# LCD_RGB.net
KiCad netlist of a schematic drawn in Altium Designer
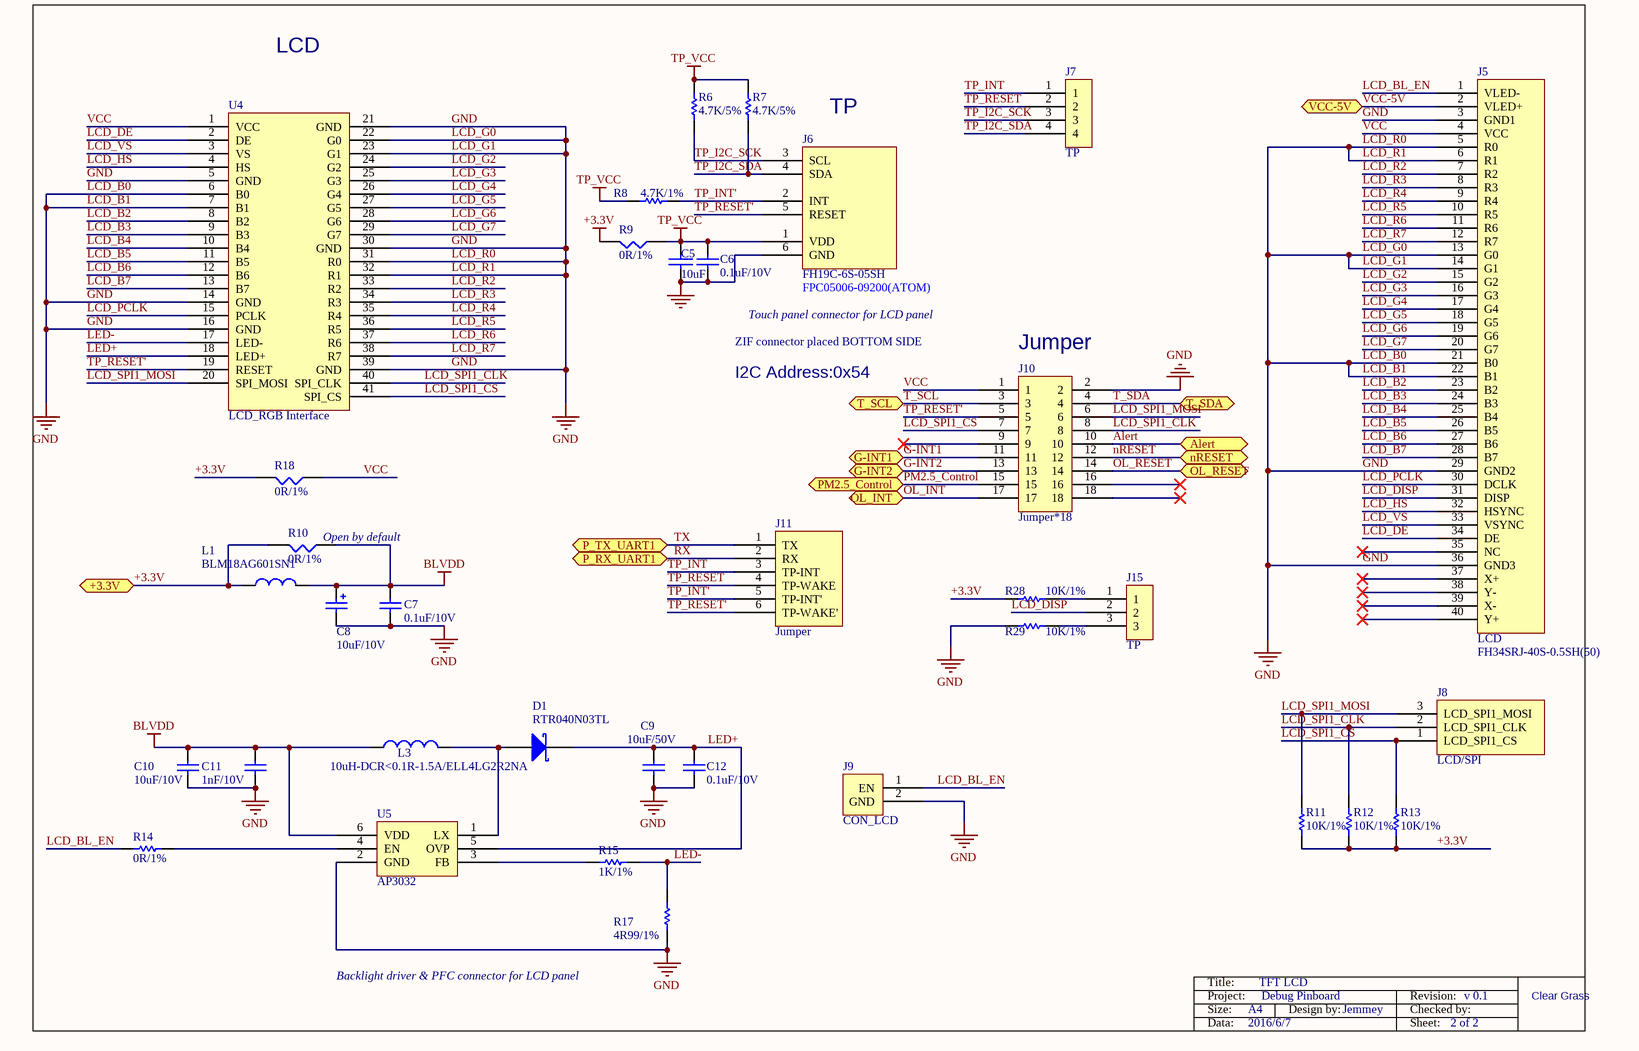
[diagram p0: LCD_RGB.SchDoc]

(export (version "E")
  (design (tool "Eeschema 10.0.6"))
  (components
    (comp (ref "C5")
      (value "10uF")
      (footprint "0603C")
      (description "厂家：Murata，型号：GRM1555C1H120JA01D")
      (libsource (lib "Amber") (part "CAP"))
    )
    (comp (ref "C6")
      (value "0.1uF/10V")
      (footprint "0402C")
      (description "Capacitor")
      (fields (field (name "PUBLISHER") "Altium Limited"))
      (libsource (lib "Miscellaneous Devices") (part "CAP"))
    )
    (comp (ref "C7")
      (value "0.1uF/10V")
      (footprint "0402C")
      (description "Capacitor")
      (fields (field (name "PUBLISHER") "Altium Limited"))
      (libsource (lib "Miscellaneous Devices") (part "Cap"))
    )
    (comp (ref "C8")
      (value "10uF/10V")
      (footprint "0603C")
      (description "Polarized Capacitor (Radial)")
      (fields (field (name "PUBLISHER") "Altium Limited"))
      (libsource (lib "Miscellaneous Devices") (part "Cap Pol1"))
    )
    (comp (ref "C9")
      (value "10uF/50V")
      (footprint "0603C")
      (description "厂家：Murata，型号：")
      (fields (field (name "PUBLISHER") "Altium Limited"))
      (libsource (lib "Miscellaneous Devices") (part "CAP"))
    )
    (comp (ref "C10")
      (value "10uF/10V")
      (footprint "0603C")
      (description "Capacitor")
      (fields (field (name "PUBLISHER") "Altium Limited"))
      (libsource (lib "Miscellaneous Devices") (part "CAP"))
    )
    (comp (ref "C11")
      (value "1nF/10V")
      (footprint "0402C")
      (description "Capacitor")
      (fields (field (name "PUBLISHER") "Altium Limited"))
      (libsource (lib "Miscellaneous Devices") (part "CAP"))
    )
    (comp (ref "C12")
      (value "0.1uF/10V")
      (footprint "0402C")
      (description "厂家：Murata，型号：")
      (fields (field (name "PUBLISHER") "Altium Limited"))
      (libsource (lib "*") (part "CAP"))
    )
    (comp (ref "D1")
      (value "RTR040N03TL")
      (footprint "TUMD2M")
      (description "Schottky Diode")
      (fields (field (name "PUBLISHER") "Altium Limited"))
      (libsource (lib "Miscellaneous Devices") (part "D Schottky"))
    )
    (comp (ref "J5")
      (value "LCD")
      (footprint "FPC_CON40-BACK-IRS")
      (libsource (lib "Debug Pinborad_1") (part "FPC60_1"))
    )
    (comp (ref "J6")
      (value "FH19C-6S-05SH")
      (footprint "FPC_CON6-BACK-MOLEX")
      (description "ZIF connector placed bottom side")
      (libsource (lib "MB1166") (part "FH19C-6S-05SH"))
    )
    (comp (ref "J7")
      (value "TP")
      (footprint "FPC_CON4-1MM-MOLEX")
      (description "Jumper")
      (libsource (lib "Bran PinBoard") (part "Jumper_uart"))
    )
    (comp (ref "J8")
      (value "LCD/SPI")
      (footprint "2.54*3")
      (description "Jumper")
      (libsource (lib "Debug Pinborad") (part "Jumper"))
    )
    (comp (ref "J9")
      (value "CON_LCD")
      (footprint "2.54*2")
      (libsource (lib "Debug Pinborad") (part "CON_LCD"))
    )
    (comp (ref "J10")
      (value "Jumper*18")
      (footprint "2.54*18")
      (libsource (lib "Bran PinBoard") (part "Jumper*18"))
    )
    (comp (ref "J11")
      (value "Jumper")
      (footprint "2.54*2 *3")
      (libsource (lib "Bran PinBoard_1") (part "Jumper_uart"))
    )
    (comp (ref "J15")
      (value "TP")
      (footprint "2.54*3")
      (description "Jumper")
      (libsource (lib "") (part "Jumper_uart_1"))
    )
    (comp (ref "L1")
      (value "BLM18AG601SN1")
      (footprint "0603R")
      (description "厂家：MURATA，型号：BLM18AG601SN1")
      (libsource (lib "Amber") (part "CHOKE"))
    )
    (comp (ref "L3")
      (value "10uH-DCR<0.1R-1.5A/ELL4LG2R2NA")
      (footprint "INDM4040X18N")
      (description "Inductor")
      (fields (field (name "PUBLISHER") "Altium Limited"))
      (libsource (lib "Miscellaneous Devices") (part "Inductor"))
    )
    (comp (ref "R6")
      (value "4.7K/5%")
      (footprint "0402R")
      (description "厂家：Yageo，型号：")
      (fields (field (name "PUBLISHER") "Altium Limited"))
      (libsource (lib "*") (part "Res1"))
    )
    (comp (ref "R7")
      (value "4.7K/5%")
      (footprint "0402R")
      (description "厂家：Yageo，型号：")
      (fields (field (name "PUBLISHER") "Altium Limited"))
      (libsource (lib "*") (part "Res1"))
    )
    (comp (ref "R8")
      (value "4.7K/1%")
      (footprint "0402R")
      (description "厂家：Yageo，型号：")
      (fields (field (name "PUBLISHER") "Altium Limited"))
      (libsource (lib "*") (part "Res1"))
    )
    (comp (ref "R9")
      (value "0R/1%")
      (footprint "0603R")
      (description "厂家：Yageo，型号：RC0402FR-070RL")
      (libsource (lib "*") (part "RES1"))
    )
    (comp (ref "R10")
      (value "0R/1%")
      (footprint "0603R")
      (description "厂家：Yageo，型号：RC0402FR-070RL")
      (libsource (lib "*") (part "RES1"))
    )
    (comp (ref "R11")
      (value "10K/1%")
      (footprint "0402R")
      (description "厂家：Yageo，型号：")
      (fields (field (name "PUBLISHER") "Altium Limited"))
      (libsource (lib "*") (part "Res1"))
    )
    (comp (ref "R12")
      (value "10K/1%")
      (footprint "0402R")
      (description "厂家：Yageo，型号：")
      (fields (field (name "PUBLISHER") "Altium Limited"))
      (libsource (lib "*") (part "Res1"))
    )
    (comp (ref "R13")
      (value "10K/1%")
      (footprint "0402R")
      (description "厂家：Yageo，型号：")
      (fields (field (name "PUBLISHER") "Altium Limited"))
      (libsource (lib "*") (part "Res1"))
    )
    (comp (ref "R14")
      (value "0R/1%")
      (footprint "0402R")
      (description "Resistor")
      (fields (field (name "PUBLISHER") "Altium Limited"))
      (libsource (lib "Miscellaneous Devices") (part "Res1"))
    )
    (comp (ref "R15")
      (value "1K/1%")
      (footprint "0402R")
      (description "Resistor")
      (fields (field (name "PUBLISHER") "Altium Limited"))
      (libsource (lib "Miscellaneous Devices") (part "Res1"))
    )
    (comp (ref "R17")
      (value "4R99/1%")
      (footprint "0402R")
      (description "Resistor")
      (fields (field (name "PUBLISHER") "Altium Limited"))
      (libsource (lib "Miscellaneous Devices") (part "Res1"))
    )
    (comp (ref "R18")
      (value "0R/1%")
      (footprint "0603R")
      (description "厂家：Yageo，型号：RC0402FR-070RL")
      (libsource (lib "*") (part "RES1"))
    )
    (comp (ref "R28")
      (value "10K/1%")
      (footprint "0402R")
      (description "厂家：Yageo，型号：")
      (fields (field (name "PUBLISHER") "Altium Limited"))
      (libsource (lib "*") (part "Res1"))
    )
    (comp (ref "R29")
      (value "10K/1%")
      (footprint "0402R")
      (description "厂家：Yageo，型号：")
      (fields (field (name "PUBLISHER") "Altium Limited"))
      (libsource (lib "*") (part "Res1"))
    )
    (comp (ref "U4")
      (value "LCD_RGB Interface")
      (footprint "FPC_CON41-0.3MM-HRS")
      (libsource (lib "Debug Pinborad_1") (part "LCD_RGB Interface"))
    )
    (comp (ref "U5")
      (value "AP3032")
      (footprint "SOT23-6-L")
      (libsource (lib "Debug Pinborad") (part "AP3032"))
    )
  )
  (nets
    (net (code "1") (name "+3.3V") (class "Default")
      (node (ref "L1") (pin "1") (pinfunction "1_1") (pintype "passive"))
      (node (ref "R10") (pin "2") (pinfunction "2_2") (pintype "passive"))
      (node (ref "R11") (pin "1") (pinfunction "1_1") (pintype "passive"))
      (node (ref "R12") (pin "1") (pinfunction "1_1") (pintype "passive"))
      (node (ref "R13") (pin "1") (pinfunction "1_1") (pintype "passive"))
      (node (ref "R18") (pin "2") (pinfunction "2_2") (pintype "passive"))
      (node (ref "R28") (pin "2") (pinfunction "2_2") (pintype "passive"))
      (node (ref "R9") (pin "2") (pinfunction "2_2") (pintype "passive"))
    )
    (net (code "2") (name "/Alert") (class "Default")
      (node (ref "J10") (pin "10") (pinfunction "10_10") (pintype "passive"))
    )
    (net (code "3") (name "/G-INT1") (class "Default")
      (node (ref "J10") (pin "11") (pinfunction "11_11") (pintype "passive"))
    )
    (net (code "4") (name "/G-INT2") (class "Default")
      (node (ref "J10") (pin "13") (pinfunction "13_13") (pintype "passive"))
    )
    (net (code "5") (name "/LCD_B2") (class "Default")
      (node (ref "J5") (pin "23") (pinfunction "B2_23") (pintype "passive"))
      (node (ref "U4") (pin "8") (pinfunction "B2_8") (pintype "passive"))
    )
    (net (code "6") (name "/LCD_B3") (class "Default")
      (node (ref "J5") (pin "24") (pinfunction "B3_24") (pintype "passive"))
      (node (ref "U4") (pin "9") (pinfunction "B3_9") (pintype "passive"))
    )
    (net (code "7") (name "/LCD_B4") (class "Default")
      (node (ref "J5") (pin "25") (pinfunction "B4_25") (pintype "passive"))
      (node (ref "U4") (pin "10") (pinfunction "B4_10") (pintype "passive"))
    )
    (net (code "8") (name "/LCD_B5") (class "Default")
      (node (ref "J5") (pin "26") (pinfunction "B5_26") (pintype "passive"))
      (node (ref "U4") (pin "11") (pinfunction "B5_11") (pintype "passive"))
    )
    (net (code "9") (name "/LCD_B6") (class "Default")
      (node (ref "J5") (pin "27") (pinfunction "B6_27") (pintype "passive"))
      (node (ref "U4") (pin "12") (pinfunction "B6_12") (pintype "passive"))
    )
    (net (code "10") (name "/LCD_B7") (class "Default")
      (node (ref "J5") (pin "28") (pinfunction "B7_28") (pintype "passive"))
      (node (ref "U4") (pin "13") (pinfunction "B7_13") (pintype "passive"))
    )
    (net (code "11") (name "/LCD_BL_EN") (class "Default")
      (node (ref "J5") (pin "1") (pinfunction "VLED-_1") (pintype "passive"))
      (node (ref "J9") (pin "1") (pinfunction "EN_1") (pintype "passive"))
      (node (ref "R14") (pin "1") (pinfunction "1_1") (pintype "passive"))
    )
    (net (code "12") (name "/LCD_DE") (class "Default")
      (node (ref "J5") (pin "34") (pinfunction "DE_34") (pintype "passive"))
      (node (ref "U4") (pin "2") (pinfunction "DE_2") (pintype "passive"))
    )
    (net (code "13") (name "/LCD_DISP") (class "Default")
      (node (ref "J15") (pin "2") (pinfunction "2_2") (pintype "passive"))
      (node (ref "J5") (pin "31") (pinfunction "DISP_31") (pintype "passive"))
    )
    (net (code "14") (name "/LCD_G2") (class "Default")
      (node (ref "J5") (pin "15") (pinfunction "G2_15") (pintype "passive"))
      (node (ref "U4") (pin "24") (pinfunction "G2_24") (pintype "passive"))
    )
    (net (code "15") (name "/LCD_G3") (class "Default")
      (node (ref "J5") (pin "16") (pinfunction "G3_16") (pintype "passive"))
      (node (ref "U4") (pin "25") (pinfunction "G3_25") (pintype "passive"))
    )
    (net (code "16") (name "/LCD_G4") (class "Default")
      (node (ref "J5") (pin "17") (pinfunction "G4_17") (pintype "passive"))
      (node (ref "U4") (pin "26") (pinfunction "G4_26") (pintype "passive"))
    )
    (net (code "17") (name "/LCD_G5") (class "Default")
      (node (ref "J5") (pin "18") (pinfunction "G5_18") (pintype "passive"))
      (node (ref "U4") (pin "27") (pinfunction "G5_27") (pintype "passive"))
    )
    (net (code "18") (name "/LCD_G6") (class "Default")
      (node (ref "J5") (pin "19") (pinfunction "G6_19") (pintype "passive"))
      (node (ref "U4") (pin "28") (pinfunction "G6_28") (pintype "passive"))
    )
    (net (code "19") (name "/LCD_G7") (class "Default")
      (node (ref "J5") (pin "20") (pinfunction "G7_20") (pintype "passive"))
      (node (ref "U4") (pin "29") (pinfunction "G7_29") (pintype "passive"))
    )
    (net (code "20") (name "/LCD_HS") (class "Default")
      (node (ref "J5") (pin "32") (pinfunction "HSYNC_32") (pintype "passive"))
      (node (ref "U4") (pin "4") (pinfunction "HS_4") (pintype "passive"))
    )
    (net (code "21") (name "/LCD_PCLK") (class "Default")
      (node (ref "J5") (pin "30") (pinfunction "DCLK_30") (pintype "passive"))
      (node (ref "U4") (pin "15") (pinfunction "PCLK_15") (pintype "passive"))
    )
    (net (code "22") (name "/LCD_R2") (class "Default")
      (node (ref "J5") (pin "7") (pinfunction "R2_7") (pintype "passive"))
      (node (ref "U4") (pin "33") (pinfunction "R2_33") (pintype "passive"))
    )
    (net (code "23") (name "/LCD_R3") (class "Default")
      (node (ref "J5") (pin "8") (pinfunction "R3_8") (pintype "passive"))
      (node (ref "U4") (pin "34") (pinfunction "R3_34") (pintype "passive"))
    )
    (net (code "24") (name "/LCD_R4") (class "Default")
      (node (ref "J5") (pin "9") (pinfunction "R4_9") (pintype "passive"))
      (node (ref "U4") (pin "35") (pinfunction "R4_35") (pintype "passive"))
    )
    (net (code "25") (name "/LCD_R5") (class "Default")
      (node (ref "J5") (pin "10") (pinfunction "R5_10") (pintype "passive"))
      (node (ref "U4") (pin "36") (pinfunction "R5_36") (pintype "passive"))
    )
    (net (code "26") (name "/LCD_R6") (class "Default")
      (node (ref "J5") (pin "11") (pinfunction "R6_11") (pintype "passive"))
      (node (ref "U4") (pin "37") (pinfunction "R6_37") (pintype "passive"))
    )
    (net (code "27") (name "/LCD_R7") (class "Default")
      (node (ref "J5") (pin "12") (pinfunction "R7_12") (pintype "passive"))
      (node (ref "U4") (pin "38") (pinfunction "R7_38") (pintype "passive"))
    )
    (net (code "28") (name "/LCD_SPI1_CLK") (class "Default")
      (node (ref "J10") (pin "8") (pinfunction "8_8") (pintype "passive"))
      (node (ref "J8") (pin "2") (pinfunction "LCD_SPI1_CLK_2") (pintype "passive"))
      (node (ref "R12") (pin "2") (pinfunction "2_2") (pintype "passive"))
      (node (ref "U4") (pin "40") (pinfunction "SPI_CLK_40") (pintype "passive"))
    )
    (net (code "29") (name "/LCD_SPI1_CS") (class "Default")
      (node (ref "J10") (pin "7") (pinfunction "7_7") (pintype "passive"))
      (node (ref "J8") (pin "1") (pinfunction "LCD_SPI1_CS_1") (pintype "passive"))
      (node (ref "R13") (pin "2") (pinfunction "2_2") (pintype "passive"))
      (node (ref "U4") (pin "41") (pinfunction "SPI_CS_41") (pintype "passive"))
    )
    (net (code "30") (name "/LCD_SPI1_MOSI") (class "Default")
      (node (ref "J10") (pin "6") (pinfunction "6_6") (pintype "passive"))
      (node (ref "J8") (pin "3") (pinfunction "LCD_SPI1_MOSI_3") (pintype "passive"))
      (node (ref "R11") (pin "2") (pinfunction "2_2") (pintype "passive"))
      (node (ref "U4") (pin "20") (pinfunction "SPI_MOSI_20") (pintype "passive"))
    )
    (net (code "31") (name "/LCD_VS") (class "Default")
      (node (ref "J5") (pin "33") (pinfunction "VSYNC_33") (pintype "passive"))
      (node (ref "U4") (pin "3") (pinfunction "VS_3") (pintype "passive"))
    )
    (net (code "32") (name "/LED+") (class "Default")
      (node (ref "C12") (pin "2") (pinfunction "2_2") (pintype "passive"))
      (node (ref "C9") (pin "1") (pinfunction "1_1") (pintype "passive"))
      (node (ref "D1") (pin "2") (pinfunction "K_2") (pintype "passive"))
      (node (ref "U4") (pin "18") (pinfunction "LED+_18") (pintype "passive"))
      (node (ref "U5") (pin "5") (pinfunction "OVP_5") (pintype "passive"))
    )
    (net (code "33") (name "/LED-") (class "Default")
      (node (ref "R15") (pin "2") (pinfunction "2_2") (pintype "passive"))
      (node (ref "R17") (pin "1") (pinfunction "1_1") (pintype "passive"))
      (node (ref "U4") (pin "17") (pinfunction "LED-_17") (pintype "passive"))
    )
    (net (code "34") (name "/OL_INT") (class "Default")
      (node (ref "J10") (pin "17") (pinfunction "17_17") (pintype "passive"))
    )
    (net (code "35") (name "/OL_RESET") (class "Default")
      (node (ref "J10") (pin "14") (pinfunction "14_14") (pintype "passive"))
    )
    (net (code "36") (name "/PM2.5_Control") (class "Default")
      (node (ref "J10") (pin "15") (pinfunction "15_15") (pintype "passive"))
    )
    (net (code "37") (name "/RX") (class "Default")
      (node (ref "J11") (pin "2") (pinfunction "RX_2") (pintype "passive"))
    )
    (net (code "38") (name "/TP_I2C_SCK") (class "Default")
      (node (ref "J6") (pin "3") (pinfunction "SCL_3") (pintype "passive"))
      (node (ref "J7") (pin "3") (pinfunction "3_3") (pintype "passive"))
      (node (ref "R6") (pin "1") (pinfunction "1_1") (pintype "passive"))
    )
    (net (code "39") (name "/TP_I2C_SDA") (class "Default")
      (node (ref "J6") (pin "4") (pinfunction "SDA_4") (pintype "passive"))
      (node (ref "J7") (pin "4") (pinfunction "4_4") (pintype "passive"))
      (node (ref "R7") (pin "1") (pinfunction "1_1") (pintype "passive"))
    )
    (net (code "40") (name "/TP_INT") (class "Default")
      (node (ref "J11") (pin "3") (pinfunction "TP-INT_3") (pintype "passive"))
      (node (ref "J7") (pin "1") (pinfunction "1_1") (pintype "passive"))
    )
    (net (code "41") (name "/TP_INT'") (class "Default")
      (node (ref "J11") (pin "5") (pinfunction "TP-INT'_5") (pintype "passive"))
      (node (ref "J6") (pin "2") (pinfunction "INT_2") (pintype "passive"))
      (node (ref "R8") (pin "2") (pinfunction "2_2") (pintype "passive"))
    )
    (net (code "42") (name "/TP_RESET") (class "Default")
      (node (ref "J11") (pin "4") (pinfunction "TP-WAKE_4") (pintype "passive"))
      (node (ref "J7") (pin "2") (pinfunction "2_2") (pintype "passive"))
    )
    (net (code "43") (name "/TP_RESET'") (class "Default")
      (node (ref "J10") (pin "5") (pinfunction "5_5") (pintype "passive"))
      (node (ref "J11") (pin "6") (pinfunction "TP-WAKE'_6") (pintype "passive"))
      (node (ref "J6") (pin "5") (pinfunction "RESET_5") (pintype "passive"))
      (node (ref "U4") (pin "19") (pinfunction "RESET_19") (pintype "passive"))
    )
    (net (code "44") (name "/TX") (class "Default")
      (node (ref "J11") (pin "1") (pinfunction "TX_1") (pintype "passive"))
    )
    (net (code "45") (name "/T_SCL") (class "Default")
      (node (ref "J10") (pin "3") (pinfunction "3_3") (pintype "passive"))
    )
    (net (code "46") (name "/T_SDA") (class "Default")
      (node (ref "J10") (pin "4") (pinfunction "4_4") (pintype "passive"))
    )
    (net (code "47") (name "/VCC") (class "Default")
      (node (ref "J10") (pin "1") (pinfunction "1_1") (pintype "passive"))
      (node (ref "J5") (pin "4") (pinfunction "VCC_4") (pintype "passive"))
      (node (ref "R18") (pin "1") (pinfunction "1_1") (pintype "passive"))
      (node (ref "U4") (pin "1") (pinfunction "VCC_1") (pintype "passive"))
    )
    (net (code "48") (name "/VCC-5V") (class "Default")
      (node (ref "J5") (pin "2") (pinfunction "VLED+_2") (pintype "passive"))
    )
    (net (code "49") (name "/nRESET") (class "Default")
      (node (ref "J10") (pin "12") (pinfunction "12_12") (pintype "passive"))
    )
    (net (code "50") (name "BLVDD") (class "Default")
      (node (ref "C10") (pin "2") (pinfunction "2_2") (pintype "passive"))
      (node (ref "C11") (pin "2") (pinfunction "2_2") (pintype "passive"))
      (node (ref "C7") (pin "1") (pinfunction "1_1") (pintype "passive"))
      (node (ref "C8") (pin "1") (pinfunction "1_1") (pintype "passive"))
      (node (ref "L1") (pin "2") (pinfunction "2_2") (pintype "passive"))
      (node (ref "L3") (pin "1") (pinfunction "1_1") (pintype "passive"))
      (node (ref "R10") (pin "1") (pinfunction "1_1") (pintype "passive"))
      (node (ref "U5") (pin "6") (pinfunction "VDD_6") (pintype "passive"))
    )
    (net (code "51") (name "GND") (class "Default")
      (node (ref "C10") (pin "1") (pinfunction "1_1") (pintype "passive"))
      (node (ref "C11") (pin "1") (pinfunction "1_1") (pintype "passive"))
      (node (ref "C12") (pin "1") (pinfunction "1_1") (pintype "passive"))
      (node (ref "C5") (pin "1") (pinfunction "1_1") (pintype "passive"))
      (node (ref "C6") (pin "1") (pinfunction "1_1") (pintype "passive"))
      (node (ref "C7") (pin "2") (pinfunction "2_2") (pintype "passive"))
      (node (ref "C8") (pin "2") (pinfunction "2_2") (pintype "passive"))
      (node (ref "C9") (pin "2") (pinfunction "2_2") (pintype "passive"))
      (node (ref "J10") (pin "2") (pinfunction "2_2") (pintype "passive"))
      (node (ref "J5") (pin "13") (pinfunction "G0_13") (pintype "passive"))
      (node (ref "J5") (pin "14") (pinfunction "G1_14") (pintype "passive"))
      (node (ref "J5") (pin "21") (pinfunction "B0_21") (pintype "passive"))
      (node (ref "J5") (pin "22") (pinfunction "B1_22") (pintype "passive"))
      (node (ref "J5") (pin "29") (pinfunction "GND2_29") (pintype "passive"))
      (node (ref "J5") (pin "3") (pinfunction "GND1_3") (pintype "passive"))
      (node (ref "J5") (pin "36") (pinfunction "GND3_36") (pintype "passive"))
      (node (ref "J5") (pin "5") (pinfunction "R0_5") (pintype "passive"))
      (node (ref "J5") (pin "6") (pinfunction "R1_6") (pintype "passive"))
      (node (ref "J6") (pin "6") (pinfunction "GND_6") (pintype "passive"))
      (node (ref "J9") (pin "2") (pinfunction "GND_2") (pintype "passive"))
      (node (ref "R17") (pin "2") (pinfunction "2_2") (pintype "passive"))
      (node (ref "R29") (pin "2") (pinfunction "2_2") (pintype "passive"))
      (node (ref "U4") (pin "14") (pinfunction "GND_14") (pintype "passive"))
      (node (ref "U4") (pin "16") (pinfunction "GND_16") (pintype "passive"))
      (node (ref "U4") (pin "21") (pinfunction "GND_21") (pintype "passive"))
      (node (ref "U4") (pin "22") (pinfunction "G0_22") (pintype "passive"))
      (node (ref "U4") (pin "23") (pinfunction "G1_23") (pintype "passive"))
      (node (ref "U4") (pin "30") (pinfunction "GND_30") (pintype "passive"))
      (node (ref "U4") (pin "31") (pinfunction "R0_31") (pintype "passive"))
      (node (ref "U4") (pin "32") (pinfunction "R1_32") (pintype "passive"))
      (node (ref "U4") (pin "39") (pinfunction "GND_39") (pintype "passive"))
      (node (ref "U4") (pin "5") (pinfunction "GND_5") (pintype "passive"))
      (node (ref "U4") (pin "6") (pinfunction "B0_6") (pintype "passive"))
      (node (ref "U4") (pin "7") (pinfunction "B1_7") (pintype "passive"))
      (node (ref "U5") (pin "2") (pinfunction "GND_2") (pintype "passive"))
    )
    (net (code "52") (name "Net-(D1-A)") (class "Default")
      (node (ref "D1") (pin "1") (pinfunction "A_1") (pintype "passive"))
      (node (ref "L3") (pin "2") (pinfunction "2_2") (pintype "passive"))
      (node (ref "U5") (pin "1") (pinfunction "LX_1") (pintype "passive"))
    )
    (net (code "53") (name "Net-(J15-Pad1)") (class "Default")
      (node (ref "J15") (pin "1") (pinfunction "1_1") (pintype "passive"))
      (node (ref "R28") (pin "1") (pinfunction "1_1") (pintype "passive"))
    )
    (net (code "54") (name "Net-(J15-Pad3)") (class "Default")
      (node (ref "J15") (pin "3") (pinfunction "3_3") (pintype "passive"))
      (node (ref "R29") (pin "1") (pinfunction "1_1") (pintype "passive"))
    )
    (net (code "55") (name "Net-(U5-EN)") (class "Default")
      (node (ref "R14") (pin "2") (pinfunction "2_2") (pintype "passive"))
      (node (ref "U5") (pin "4") (pinfunction "EN_4") (pintype "passive"))
    )
    (net (code "56") (name "Net-(U5-FB)") (class "Default")
      (node (ref "R15") (pin "1") (pinfunction "1_1") (pintype "passive"))
      (node (ref "U5") (pin "3") (pinfunction "FB_3") (pintype "passive"))
    )
    (net (code "57") (name "TP_VCC") (class "Default")
      (node (ref "C5") (pin "2") (pinfunction "2_2") (pintype "passive"))
      (node (ref "C6") (pin "2") (pinfunction "2_2") (pintype "passive"))
      (node (ref "J6") (pin "1") (pinfunction "VDD_1") (pintype "passive"))
      (node (ref "R6") (pin "2") (pinfunction "2_2") (pintype "passive"))
      (node (ref "R7") (pin "2") (pinfunction "2_2") (pintype "passive"))
      (node (ref "R8") (pin "1") (pinfunction "1_1") (pintype "passive"))
      (node (ref "R9") (pin "1") (pinfunction "1_1") (pintype "passive"))
    )
    (net (code "58") (name "unconnected-(J5-NC-Pad35)") (class "Default")
      (node (ref "J5") (pin "35") (pinfunction "NC_35") (pintype "passive+no_connect"))
    )
    (net (code "59") (name "unconnected-(J5-X+-Pad37)") (class "Default")
      (node (ref "J5") (pin "37") (pinfunction "X+_37") (pintype "passive+no_connect"))
    )
    (net (code "60") (name "unconnected-(J5-X--Pad39)") (class "Default")
      (node (ref "J5") (pin "39") (pinfunction "X-_39") (pintype "passive+no_connect"))
    )
    (net (code "61") (name "unconnected-(J5-Y+-Pad40)") (class "Default")
      (node (ref "J5") (pin "40") (pinfunction "Y+_40") (pintype "passive+no_connect"))
    )
    (net (code "62") (name "unconnected-(J5-Y--Pad38)") (class "Default")
      (node (ref "J5") (pin "38") (pinfunction "Y-_38") (pintype "passive+no_connect"))
    )
    (net (code "63") (name "unconnected-(J10-Pad9)") (class "Default")
      (node (ref "J10") (pin "9") (pinfunction "9_9") (pintype "passive+no_connect"))
    )
    (net (code "64") (name "unconnected-(J10-Pad16)") (class "Default")
      (node (ref "J10") (pin "16") (pinfunction "16_16") (pintype "passive+no_connect"))
    )
    (net (code "65") (name "unconnected-(J10-Pad18)") (class "Default")
      (node (ref "J10") (pin "18") (pinfunction "18_18") (pintype "passive+no_connect"))
    )
  )
)
